# MixerHF.net
KiCad netlist of a schematic drawn in Altium Designer
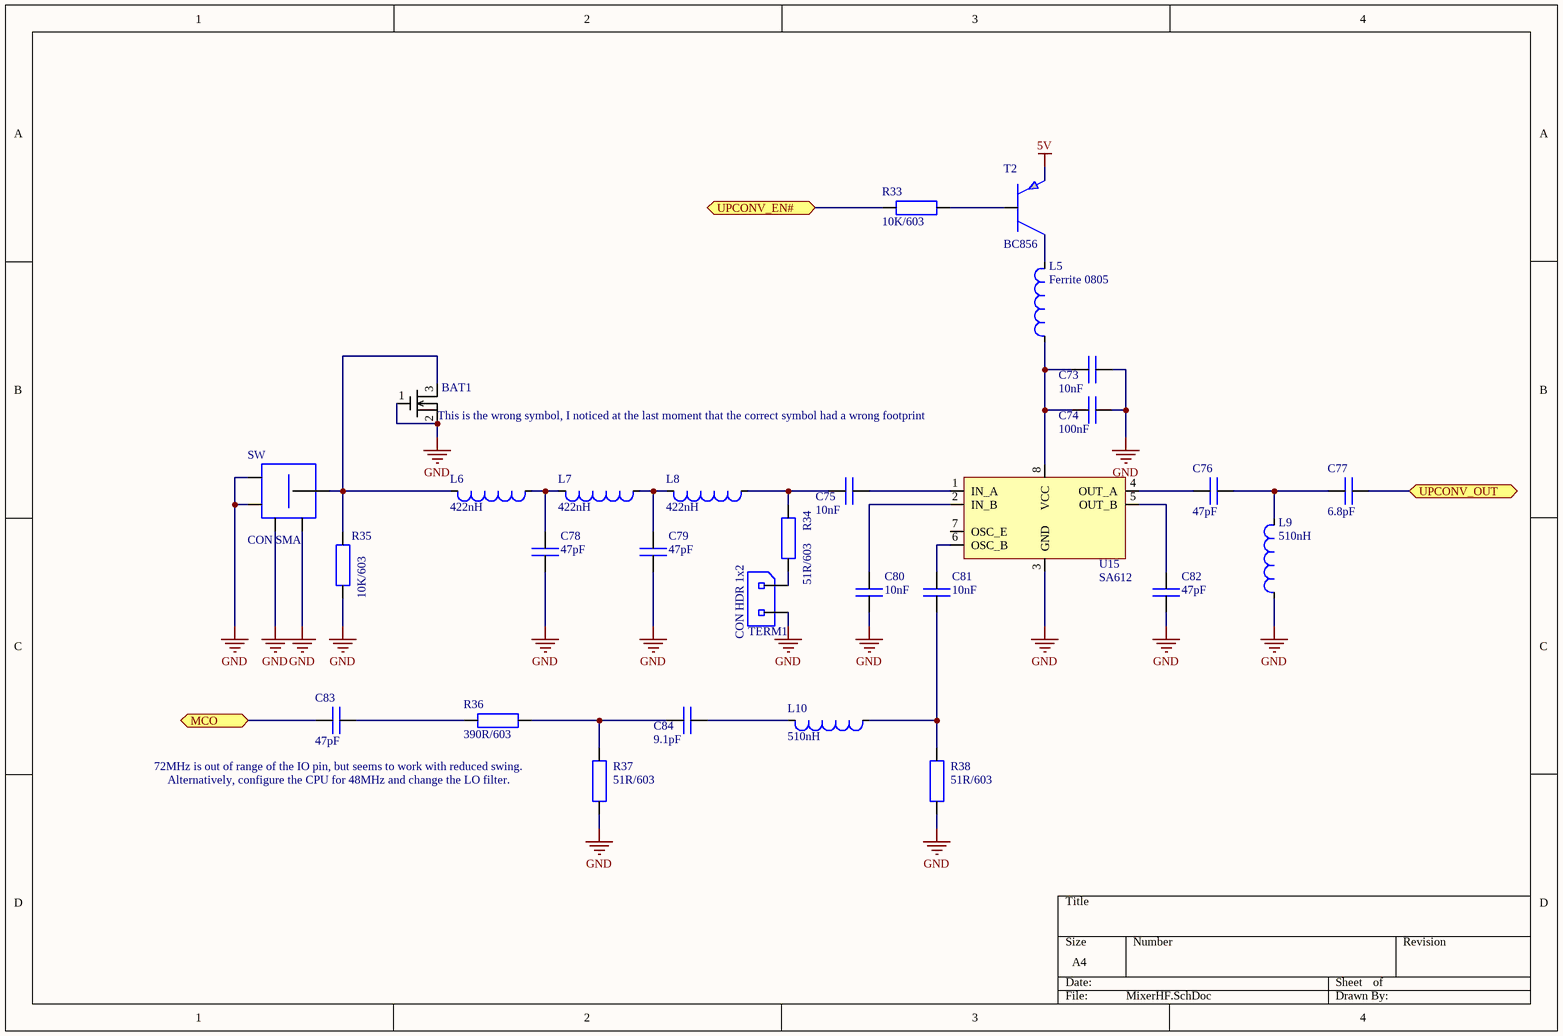
[diagram p0: MixerHF.SchDoc]

(export (version "E")
  (design (tool "Eeschema 10.0.6"))
  (components
    (comp (ref "BAT1")
      (value "~")
      (footprint "SOT95P230X110-3N")
      (libsource (lib "library") (part "NX3008NBK"))
    )
    (comp (ref "C73")
      (value "10nF")
      (footprint "smd C0603_0.80")
      (description "smd capaciteit, verp.0603, 100nF")
      (fields (field (name "PART NUMBER") "CSMD603/100nF"))
      (libsource (lib "CDE_Library") (part "CSMD603/100nF"))
    )
    (comp (ref "C74")
      (value "100nF")
      (footprint "smd C0603_0.80")
      (description "smd capaciteit, verp.0603, 100nF")
      (fields (field (name "PART NUMBER") "CSMD603/100nF"))
      (libsource (lib "CDE_Library") (part "CSMD603/100nF"))
    )
    (comp (ref "C75")
      (value "10nF")
      (footprint "smd C0603_0.80")
      (description "smd capaciteit, verp.0603, 100nF")
      (fields (field (name "PART NUMBER") "CSMD603/100nF"))
      (libsource (lib "CDE_Library") (part "CSMD603/100nF"))
    )
    (comp (ref "C76")
      (value "47pF")
      (footprint "smd C0603_0.80")
      (description "smd capaciteit, verp.0603, 10pF")
      (fields (field (name "PART NUMBER") "CSMD603/10pF"))
      (libsource (lib "CDE_Library") (part "CSMD603/10pF"))
    )
    (comp (ref "C77")
      (value "6.8pF")
      (footprint "smd C0603_0.80")
      (description "smd capaciteit, verp.0603, 10pF")
      (fields (field (name "PART NUMBER") "CSMD603/10pF"))
      (libsource (lib "CDE_Library") (part "CSMD603/10pF"))
    )
    (comp (ref "C78")
      (value "47pF")
      (footprint "smd C0603_0.80")
      (description "smd capaciteit, verp.0603, 10pF")
      (fields (field (name "PART NUMBER") "CSMD603/10pF"))
      (libsource (lib "CDE_Library") (part "CSMD603/10pF"))
    )
    (comp (ref "C79")
      (value "47pF")
      (footprint "smd C0603_0.80")
      (description "smd capaciteit, verp.0603, 10pF")
      (fields (field (name "PART NUMBER") "CSMD603/10pF"))
      (libsource (lib "CDE_Library") (part "CSMD603/10pF"))
    )
    (comp (ref "C80")
      (value "10nF")
      (footprint "smd C0603_0.80")
      (description "smd capaciteit, verp.0603, 100nF")
      (fields (field (name "PART NUMBER") "CSMD603/100nF"))
      (libsource (lib "CDE_Library") (part "CSMD603/100nF"))
    )
    (comp (ref "C81")
      (value "10nF")
      (footprint "smd C0603_0.80")
      (description "smd capaciteit, verp.0603, 100nF")
      (fields (field (name "PART NUMBER") "CSMD603/100nF"))
      (libsource (lib "CDE_Library") (part "CSMD603/100nF"))
    )
    (comp (ref "C82")
      (value "47pF")
      (footprint "smd C0603_0.80")
      (description "smd capaciteit, verp.0603, 10pF")
      (fields (field (name "PART NUMBER") "CSMD603/10pF"))
      (libsource (lib "CDE_Library") (part "CSMD603/10pF"))
    )
    (comp (ref "C83")
      (value "47pF")
      (footprint "smd C0603_0.80")
      (description "smd capaciteit, verp.0603, 10pF")
      (fields (field (name "PART NUMBER") "CSMD603/10pF"))
      (libsource (lib "CDE_Library") (part "CSMD603/10pF"))
    )
    (comp (ref "C84")
      (value "9.1pF")
      (footprint "smd C0603_0.80")
      (description "smd capaciteit, verp.0603, 100nF")
      (fields (field (name "PART NUMBER") "CSMD603/100nF"))
      (libsource (lib "CDE_Library") (part "CSMD603/100nF"))
    )
    (comp (ref "L5")
      (value "Ferrite 0805")
      (footprint "smd C0805")
      (description "Ferrite bead, 0805 package")
      (libsource (lib "CDE_Library") (part "Ferrite 0805"))
    )
    (comp (ref "L6")
      (value "422nH")
      (footprint "smd C0805")
      (description "smd spoel, verpakking 805, 250nH")
      (libsource (lib "CDE_Library") (part "SPL805/250nH"))
    )
    (comp (ref "L7")
      (value "422nH")
      (footprint "smd C0805")
      (description "smd spoel, verpakking 805, 250nH")
      (libsource (lib "CDE_Library") (part "SPL805/250nH"))
    )
    (comp (ref "L8")
      (value "422nH")
      (footprint "smd C0805")
      (description "smd spoel, verpakking 805, 250nH")
      (libsource (lib "CDE_Library") (part "SPL805/250nH"))
    )
    (comp (ref "L9")
      (value "510nH")
      (footprint "smd C0805")
      (description "smd spoel, verpakking 805, 250nH")
      (libsource (lib "CDE_Library") (part "SPL805/250nH"))
    )
    (comp (ref "L10")
      (value "510nH")
      (footprint "smd C0805")
      (description "smd spoel, verpakking 805, 250nH")
      (libsource (lib "CDE_Library") (part "SPL805/250nH"))
    )
    (comp (ref "R33")
      (value "10K/603")
      (footprint "smd C0603_0.45")
      (description "weerstand SMD603, 10K")
      (libsource (lib "CDE_Library") (part "10K/603"))
    )
    (comp (ref "R34")
      (value "51R/603")
      (footprint "smd C0603_0.45")
      (description "weerstand SMD603, 51R")
      (libsource (lib "CDE_Library") (part "51R/603"))
    )
    (comp (ref "R35")
      (value "10K/603")
      (footprint "smd C0603_0.45")
      (description "weerstand SMD603, 10K")
      (libsource (lib "CDE_Library") (part "10K/603"))
    )
    (comp (ref "R36")
      (value "390R/603")
      (footprint "smd C0603_0.45")
      (description "weerstand SMD603, 390R")
      (libsource (lib "CDE_Library") (part "390R/603"))
    )
    (comp (ref "R37")
      (value "51R/603")
      (footprint "smd C0603_0.45")
      (description "weerstand SMD603, 51R")
      (libsource (lib "CDE_Library") (part "51R/603"))
    )
    (comp (ref "R38")
      (value "51R/603")
      (footprint "smd C0603_0.45")
      (description "weerstand SMD603, 51R")
      (libsource (lib "CDE_Library") (part "51R/603"))
    )
    (comp (ref "SW")
      (value "CON SMA")
      (footprint "con SMA (recht)")
      (description "SMA connector, rechtop")
      (libsource (lib "CDE_Library") (part "CON SMA"))
    )
    (comp (ref "T2")
      (value "BC856")
      (footprint "smd SOT-23")
      (description "PNP transistor, smd")
      (libsource (lib "CDE_Library") (part "BC856"))
    )
    (comp (ref "TERM1")
      (value "CON HDR 1x2")
      (footprint "hdr 1x2")
      (description "pcb header recht 1x2  pitch 100mil")
      (libsource (lib "CDE_Library") (part "CON HDR 1x2"))
    )
    (comp (ref "U15")
      (value "SA612")
      (footprint "SOIC127P600X175-8N")
      (libsource (lib "library") (part "SA612"))
    )
  )
  (nets
    (net (code "1") (name "/MCO") (class "Default") (node (ref "C83") (pin "2") (pintype "passive")))
    (net (code "2") (name "/UPCONV_EN#") (class "Default") (node (ref "R33") (pin "1") (pintype "passive")))
    (net (code "3") (name "/UPCONV_OUT") (class "Default") (node (ref "C77") (pin "2") (pintype "passive")))
    (net (code "4") (name "5V") (class "Default") (node (ref "T2") (pin "2") (pintype "passive")))
    (net (code "5") (name "GND") (class "Default")
      (node (ref "BAT1") (pin "1") (pinfunction "G_1") (pintype "passive"))
      (node (ref "BAT1") (pin "2") (pinfunction "S_2") (pintype "passive"))
      (node (ref "C73") (pin "1") (pintype "passive"))
      (node (ref "C74") (pin "1") (pintype "passive"))
      (node (ref "C78") (pin "1") (pintype "passive"))
      (node (ref "C79") (pin "1") (pintype "passive"))
      (node (ref "C80") (pin "2") (pintype "passive"))
      (node (ref "C82") (pin "1") (pintype "passive"))
      (node (ref "L9") (pin "1") (pintype "passive"))
      (node (ref "R35") (pin "1") (pintype "passive"))
      (node (ref "R37") (pin "2") (pintype "passive"))
      (node (ref "R38") (pin "2") (pintype "passive"))
      (node (ref "SW") (pin "2") (pintype "passive"))
      (node (ref "SW") (pin "3") (pintype "passive"))
      (node (ref "SW") (pin "4") (pintype "passive"))
      (node (ref "SW") (pin "5") (pintype "passive"))
      (node (ref "TERM1") (pin "2") (pintype "passive"))
      (node (ref "U15") (pin "3") (pinfunction "GND_3") (pintype "passive"))
    )
    (net (code "6") (name "Net-(BAT1-D)") (class "Default")
      (node (ref "BAT1") (pin "3") (pinfunction "D_3") (pintype "passive"))
      (node (ref "L6") (pin "2") (pintype "passive"))
      (node (ref "R35") (pin "2") (pintype "passive"))
      (node (ref "SW") (pin "1") (pintype "passive"))
    )
    (net (code "7") (name "Net-(C75-Pad2)") (class "Default")
      (node (ref "C75") (pin "2") (pintype "passive"))
      (node (ref "L8") (pin "1") (pintype "passive"))
      (node (ref "R34") (pin "2") (pintype "passive"))
    )
    (net (code "8") (name "Net-(C76-Pad2)") (class "Default")
      (node (ref "C76") (pin "2") (pintype "passive"))
      (node (ref "C77") (pin "1") (pintype "passive"))
      (node (ref "L9") (pin "2") (pintype "passive"))
    )
    (net (code "9") (name "Net-(C78-Pad2)") (class "Default")
      (node (ref "C78") (pin "2") (pintype "passive"))
      (node (ref "L6") (pin "1") (pintype "passive"))
      (node (ref "L7") (pin "2") (pintype "passive"))
    )
    (net (code "10") (name "Net-(C79-Pad2)") (class "Default")
      (node (ref "C79") (pin "2") (pintype "passive"))
      (node (ref "L7") (pin "1") (pintype "passive"))
      (node (ref "L8") (pin "2") (pintype "passive"))
    )
    (net (code "11") (name "Net-(C81-Pad2)") (class "Default")
      (node (ref "C81") (pin "2") (pintype "passive"))
      (node (ref "L10") (pin "1") (pintype "passive"))
      (node (ref "R38") (pin "1") (pintype "passive"))
    )
    (net (code "12") (name "Net-(C83-Pad1)") (class "Default")
      (node (ref "C83") (pin "1") (pintype "passive"))
      (node (ref "R36") (pin "2") (pintype "passive"))
    )
    (net (code "13") (name "Net-(C84-Pad1)") (class "Default")
      (node (ref "C84") (pin "1") (pintype "passive"))
      (node (ref "L10") (pin "2") (pintype "passive"))
    )
    (net (code "14") (name "Net-(C84-Pad2)") (class "Default")
      (node (ref "C84") (pin "2") (pintype "passive"))
      (node (ref "R36") (pin "1") (pintype "passive"))
      (node (ref "R37") (pin "1") (pintype "passive"))
    )
    (net (code "15") (name "Net-(L5-Pad2)") (class "Default")
      (node (ref "L5") (pin "2") (pintype "passive"))
      (node (ref "T2") (pin "3") (pintype "passive"))
    )
    (net (code "16") (name "Net-(R33-Pad2)") (class "Default")
      (node (ref "R33") (pin "2") (pintype "passive"))
      (node (ref "T2") (pin "1") (pintype "passive"))
    )
    (net (code "17") (name "Net-(R34-Pad1)") (class "Default")
      (node (ref "R34") (pin "1") (pintype "passive"))
      (node (ref "TERM1") (pin "1") (pintype "passive"))
    )
    (net (code "18") (name "Net-(U15-IN_A)") (class "Default")
      (node (ref "C75") (pin "1") (pintype "passive"))
      (node (ref "U15") (pin "1") (pinfunction "IN_A_1") (pintype "passive"))
    )
    (net (code "19") (name "Net-(U15-IN_B)") (class "Default")
      (node (ref "C80") (pin "1") (pintype "passive"))
      (node (ref "U15") (pin "2") (pinfunction "IN_B_2") (pintype "passive"))
    )
    (net (code "20") (name "Net-(U15-OSC_B)") (class "Default")
      (node (ref "C81") (pin "1") (pintype "passive"))
      (node (ref "U15") (pin "6") (pinfunction "OSC_B_6") (pintype "passive"))
    )
    (net (code "21") (name "Net-(U15-OUT_A)") (class "Default")
      (node (ref "C76") (pin "1") (pintype "passive"))
      (node (ref "U15") (pin "4") (pinfunction "OUT_A_4") (pintype "passive"))
    )
    (net (code "22") (name "Net-(U15-OUT_B)") (class "Default")
      (node (ref "C82") (pin "2") (pintype "passive"))
      (node (ref "U15") (pin "5") (pinfunction "OUT_B_5") (pintype "passive"))
    )
    (net (code "23") (name "Net-(U15-VCC)") (class "Default")
      (node (ref "C73") (pin "2") (pintype "passive"))
      (node (ref "C74") (pin "2") (pintype "passive"))
      (node (ref "L5") (pin "1") (pintype "passive"))
      (node (ref "U15") (pin "8") (pinfunction "VCC_8") (pintype "passive"))
    )
    (net (code "24") (name "unconnected-(U15-OSC_E-Pad7)") (class "Default")
      (node (ref "U15") (pin "7") (pinfunction "OSC_E_7") (pintype "passive"))
    )
  )
)
